# VF_Sine_CPU_Mainboard2.net
KiCad netlist of a schematic drawn in EAGLE
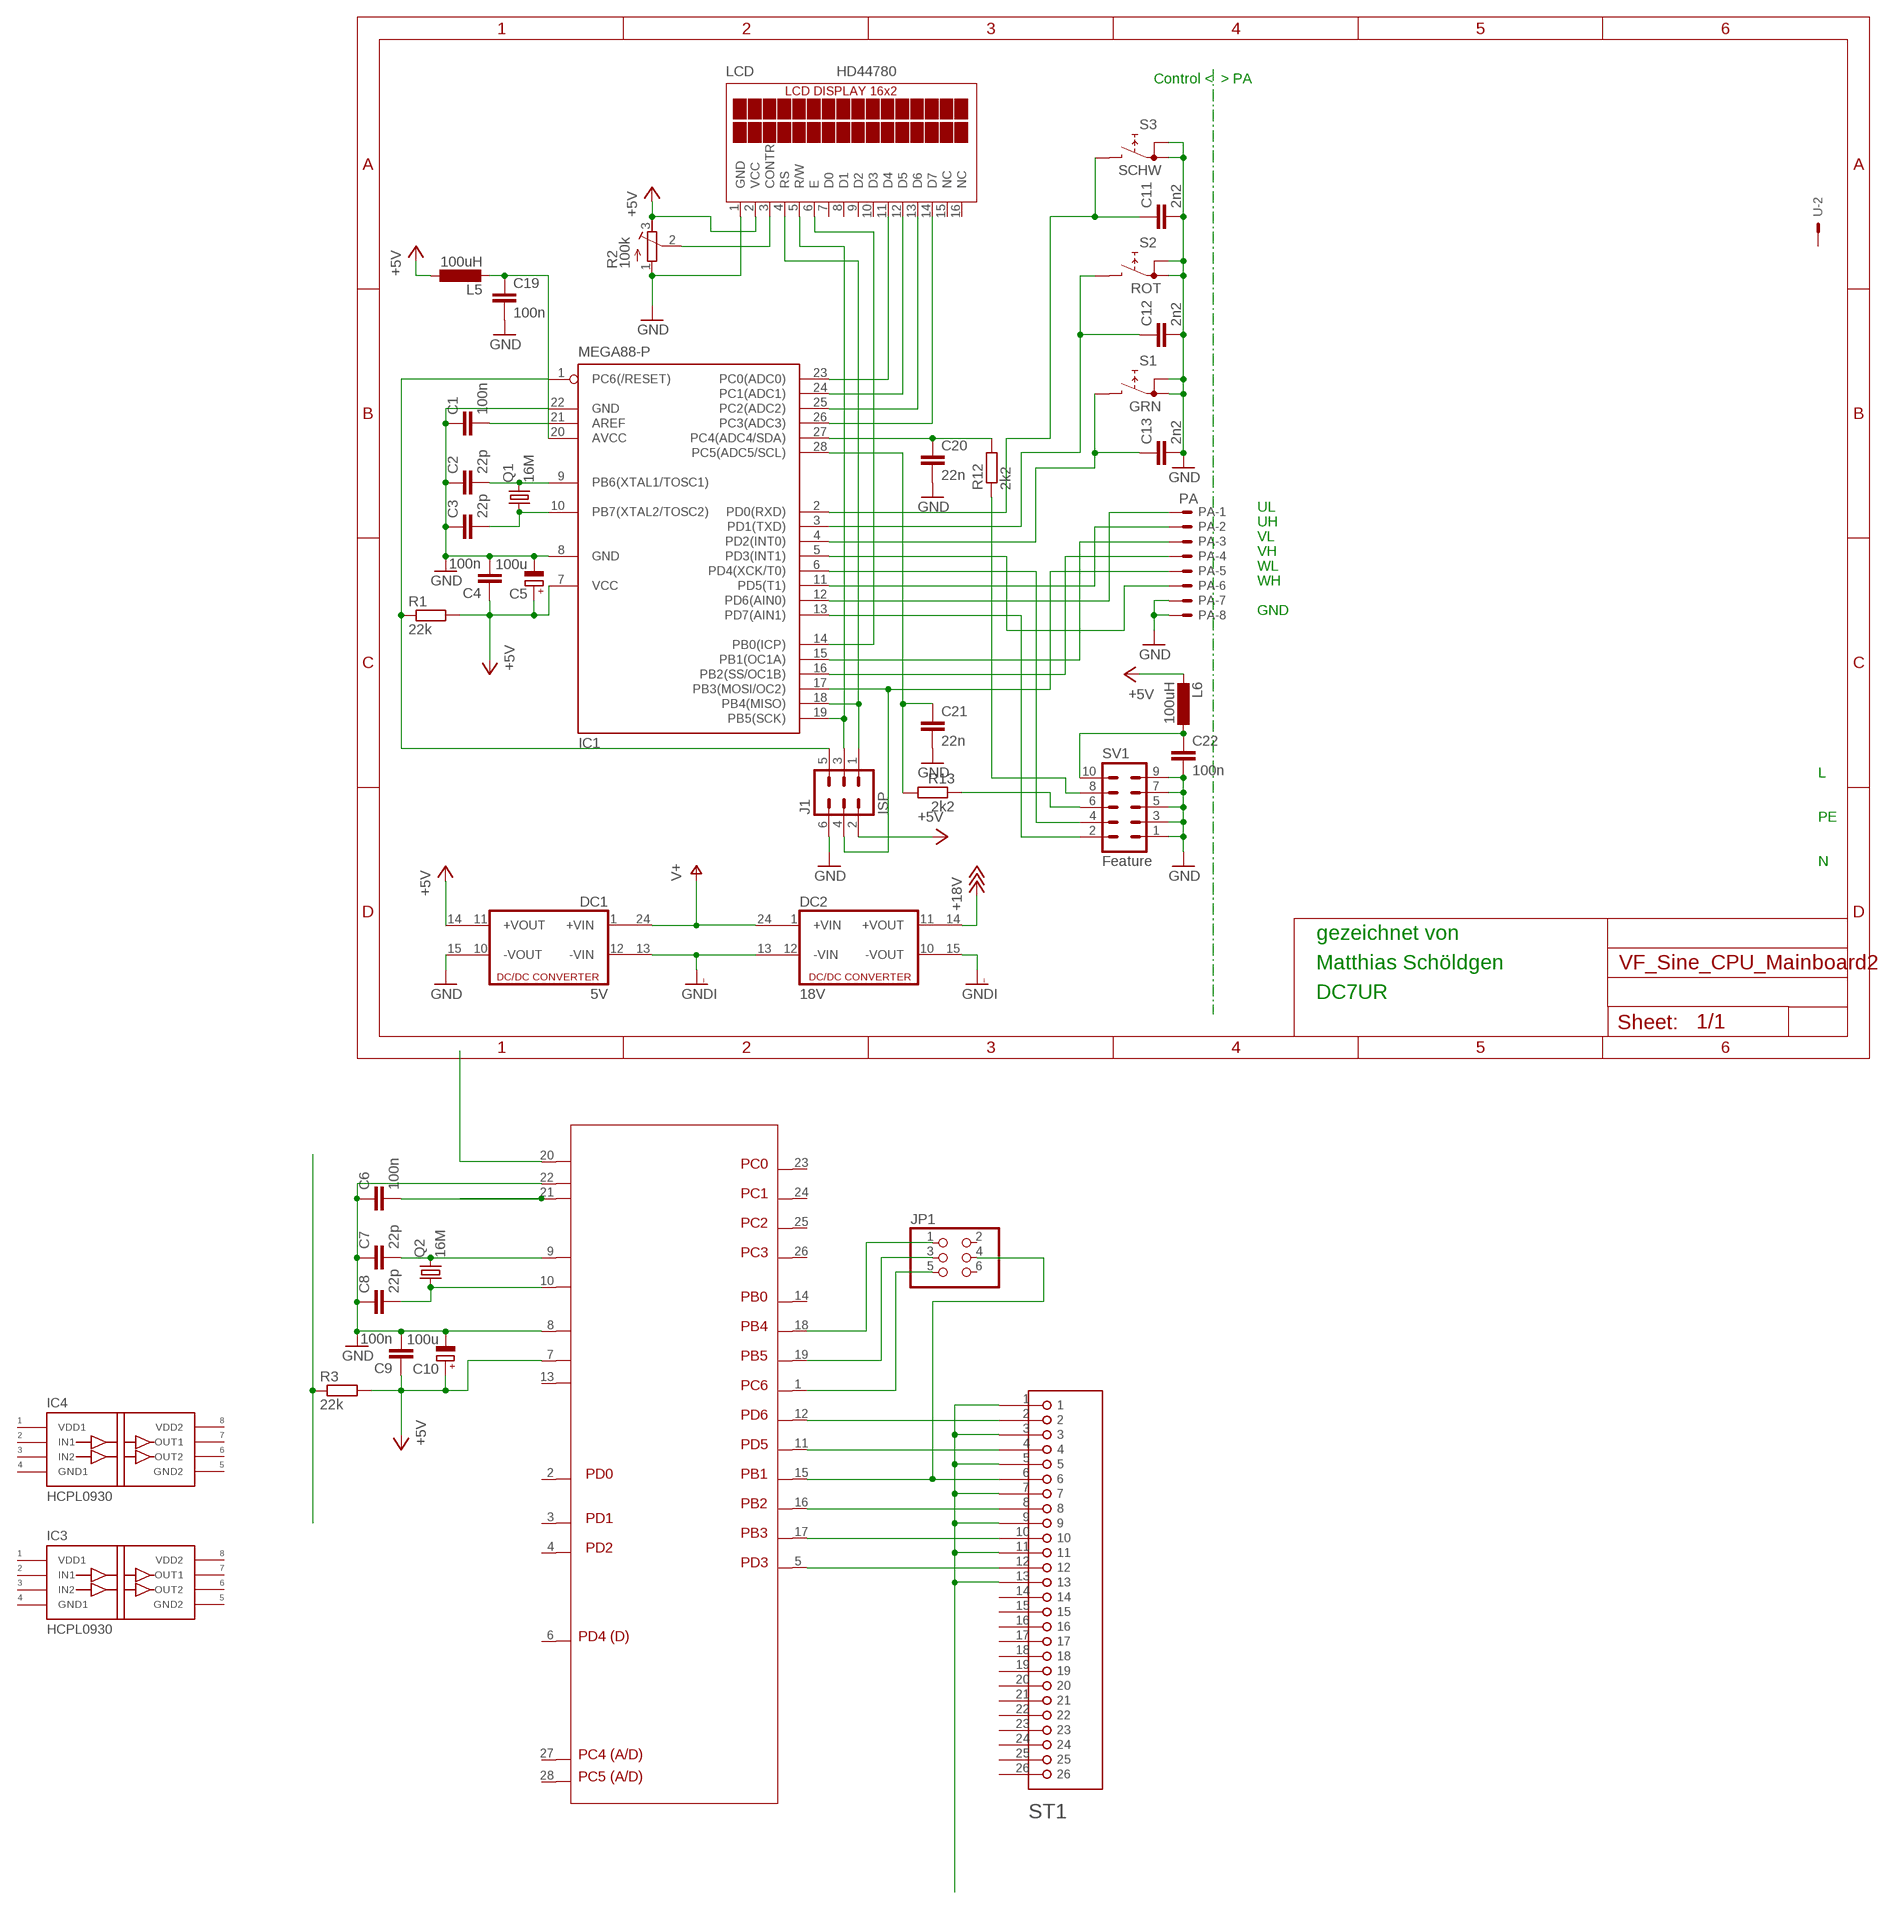
[diagram p0: schematic, sheet 1]

(export (version "E")
  (design (tool "Eeschema 10.0.6"))
  (components
    (comp (ref "C1")
      (value "100n")
      (footprint "eagle-import:C025-025X050")
      (libsource (lib "eagle-import") (part "C-EU025-025X050"))
    )
    (comp (ref "C2")
      (value "22p")
      (footprint "eagle-import:C025-025X050")
      (libsource (lib "eagle-import") (part "C-EU025-025X050"))
    )
    (comp (ref "C3")
      (value "22p")
      (footprint "eagle-import:C025-025X050")
      (libsource (lib "eagle-import") (part "C-EU025-025X050"))
    )
    (comp (ref "C4")
      (value "100n")
      (footprint "eagle-import:C025-025X050")
      (libsource (lib "eagle-import") (part "C-EU025-025X050"))
    )
    (comp (ref "C5")
      (value "100u")
      (footprint "eagle-import:B45181A")
      (libsource (lib "eagle-import") (part "CPOL-EUB45181A"))
    )
    (comp (ref "C6")
      (value "100n")
      (footprint "eagle-import:C025-025X050")
      (libsource (lib "eagle-import") (part "C-EU025-025X050"))
    )
    (comp (ref "C7")
      (value "22p")
      (footprint "eagle-import:C025-025X050")
      (libsource (lib "eagle-import") (part "C-EU025-025X050"))
    )
    (comp (ref "C8")
      (value "22p")
      (footprint "eagle-import:C025-025X050")
      (libsource (lib "eagle-import") (part "C-EU025-025X050"))
    )
    (comp (ref "C9")
      (value "100n")
      (footprint "eagle-import:C025-025X050")
      (libsource (lib "eagle-import") (part "C-EU025-025X050"))
    )
    (comp (ref "C10")
      (value "100u")
      (footprint "eagle-import:B45181A")
      (libsource (lib "eagle-import") (part "CPOL-EUB45181A"))
    )
    (comp (ref "C11")
      (value "2n2")
      (footprint "eagle-import:C025-025X050")
      (libsource (lib "eagle-import") (part "C-EU025-025X050"))
    )
    (comp (ref "C12")
      (value "2n2")
      (footprint "eagle-import:C025-025X050")
      (libsource (lib "eagle-import") (part "C-EU025-025X050"))
    )
    (comp (ref "C13")
      (value "2n2")
      (footprint "eagle-import:C025-025X050")
      (libsource (lib "eagle-import") (part "C-EU025-025X050"))
    )
    (comp (ref "C19")
      (value "100n")
      (footprint "eagle-import:C050-030X075")
      (libsource (lib "eagle-import") (part "C-EU050-030X075"))
    )
    (comp (ref "C20")
      (value "22n")
      (footprint "eagle-import:C025-024X044")
      (libsource (lib "eagle-import") (part "C-EU025-024X044"))
    )
    (comp (ref "C21")
      (value "22n")
      (footprint "eagle-import:C025-024X044")
      (libsource (lib "eagle-import") (part "C-EU025-024X044"))
    )
    (comp (ref "C22")
      (value "100n")
      (footprint "eagle-import:C025-025X050")
      (libsource (lib "eagle-import") (part "C-EU025-025X050"))
    )
    (comp (ref "DC1")
      (value "5V")
      (footprint "eagle-import:CMK")
      (libsource (lib "eagle-import") (part "DC213R"))
    )
    (comp (ref "DC2")
      (value "18V")
      (footprint "eagle-import:CMK")
      (libsource (lib "eagle-import") (part "DC213R"))
    )
    (comp (ref "IC1")
      (value "MEGA88-P")
      (footprint "eagle-import:DIL28-3")
      (libsource (lib "eagle-import") (part "MEGA8-P"))
    )
    (comp (ref "IC2")
      (value "ATMEGA328P_VAR")
      (footprint "eagle-import:DIL-28S")
      (libsource (lib "eagle-import") (part "ATMEGA328P_VAR"))
    )
    (comp (ref "IC3")
      (value "HCPL0930")
      (footprint "eagle-import:SO8")
      (libsource (lib "eagle-import") (part "HCPL0930"))
    )
    (comp (ref "IC4")
      (value "HCPL0930")
      (footprint "eagle-import:SO8")
      (libsource (lib "eagle-import") (part "HCPL0930"))
    )
    (comp (ref "J1")
      (value "ISP")
      (footprint "eagle-import:ML6")
      (libsource (lib "eagle-import") (part "ML6"))
    )
    (comp (ref "JP1")
      (value "PINHD-2X3")
      (footprint "eagle-import:2X03")
      (libsource (lib "eagle-import") (part "PINHD-2X3"))
    )
    (comp (ref "L5")
      (value "100uH")
      (footprint "eagle-import:0204_5")
      (libsource (lib "eagle-import") (part "L-EU0204/5"))
    )
    (comp (ref "L6")
      (value "100uH")
      (footprint "eagle-import:0204_5")
      (libsource (lib "eagle-import") (part "L-EU0204/5"))
    )
    (comp (ref "LCD")
      (value "HD44780")
      (footprint "eagle-import:TUXGR_16X2_R2")
      (libsource (lib "eagle-import") (part "TUXGR_16X2_R2"))
    )
    (comp (ref "PA")
      (value "PA")
      (footprint "eagle-import:22-23-2081")
      (libsource (lib "eagle-import") (part "22-23-2081"))
    )
    (comp (ref "Q1")
      (value "16M")
      (footprint "eagle-import:HC49_S")
      (libsource (lib "eagle-import") (part "CRYSTALHC49S"))
    )
    (comp (ref "Q2")
      (value "16M")
      (footprint "eagle-import:HC49_S")
      (libsource (lib "eagle-import") (part "CRYSTALHC49S"))
    )
    (comp (ref "R1")
      (value "22k")
      (footprint "eagle-import:0207_2V")
      (libsource (lib "eagle-import") (part "R-EU_0207/2V"))
    )
    (comp (ref "R2")
      (value "100k")
      (footprint "eagle-import:RTRIM4G_J")
      (libsource (lib "eagle-import") (part "R-TRIMM4G/J"))
    )
    (comp (ref "R3")
      (value "22k")
      (footprint "eagle-import:0207_2V")
      (libsource (lib "eagle-import") (part "R-EU_0207/2V"))
    )
    (comp (ref "R12")
      (value "2k2")
      (footprint "eagle-import:0204_5")
      (libsource (lib "eagle-import") (part "R-EU_0204/5"))
    )
    (comp (ref "R13")
      (value "2k2")
      (footprint "eagle-import:0204_5")
      (libsource (lib "eagle-import") (part "R-EU_0204/5"))
    )
    (comp (ref "S1")
      (value "GRN")
      (footprint "eagle-import:RDT1034")
      (libsource (lib "eagle-import") (part "RDT1034"))
    )
    (comp (ref "S2")
      (value "ROT")
      (footprint "eagle-import:RDT1034")
      (libsource (lib "eagle-import") (part "RDT1034"))
    )
    (comp (ref "S3")
      (value "SCHW")
      (footprint "eagle-import:RDT1034")
      (libsource (lib "eagle-import") (part "RDT1034"))
    )
    (comp (ref "ST1")
      (value "HD-26")
      (footprint "eagle-import:HD-26")
      (libsource (lib "eagle-import") (part "HD-26"))
    )
    (comp (ref "SV1")
      (value "Feature")
      (footprint "eagle-import:ML10")
      (libsource (lib "eagle-import") (part "ML10"))
    )
    (comp (ref "U")
      (value "5566-2")
      (footprint "eagle-import:5566-2")
      (libsource (lib "eagle-import") (part "5566-2"))
    )
  )
  (nets
    (net (code "1") (name "+5V") (class "Default")
      (node (ref "C10") (pin "+") (pinfunction "+_+") (pintype "passive"))
      (node (ref "C4") (pin "1") (pinfunction "1_1") (pintype "passive"))
      (node (ref "C5") (pin "+") (pinfunction "+_+") (pintype "passive"))
      (node (ref "C9") (pin "1") (pinfunction "1_1") (pintype "passive"))
      (node (ref "DC1") (pin "14") (pinfunction "+VOUT1_14") (pintype "passive"))
      (node (ref "IC1") (pin "7") (pinfunction "VCC_7") (pintype "power_in"))
      (node (ref "IC2") (pin "7") (pinfunction "SK1_7") (pintype "passive"))
      (node (ref "J1") (pin "2") (pinfunction "2_2") (pintype "passive"))
      (node (ref "L5") (pin "1") (pinfunction "1_1") (pintype "passive"))
      (node (ref "L6") (pin "2") (pinfunction "2_2") (pintype "passive"))
      (node (ref "LCD") (pin "2") (pinfunction "VCC_2") (pintype "power_in"))
      (node (ref "R1") (pin "2") (pinfunction "2_2") (pintype "passive"))
      (node (ref "R2") (pin "3") (pinfunction "A_3") (pintype "passive"))
      (node (ref "R3") (pin "2") (pinfunction "2_2") (pintype "passive"))
    )
    (net (code "2") (name "+18V") (class "Default")
      (node (ref "DC2") (pin "14") (pinfunction "+VOUT1_14") (pintype "passive"))
    )
    (net (code "3") (name "GND") (class "Default")
      (node (ref "C1") (pin "1") (pinfunction "1_1") (pintype "passive"))
      (node (ref "C10") (pin "-") (pinfunction "-_-") (pintype "passive"))
      (node (ref "C11") (pin "2") (pinfunction "2_2") (pintype "passive"))
      (node (ref "C12") (pin "2") (pinfunction "2_2") (pintype "passive"))
      (node (ref "C13") (pin "2") (pinfunction "2_2") (pintype "passive"))
      (node (ref "C19") (pin "2") (pinfunction "2_2") (pintype "passive"))
      (node (ref "C2") (pin "1") (pinfunction "1_1") (pintype "passive"))
      (node (ref "C20") (pin "2") (pinfunction "2_2") (pintype "passive"))
      (node (ref "C21") (pin "2") (pinfunction "2_2") (pintype "passive"))
      (node (ref "C22") (pin "2") (pinfunction "2_2") (pintype "passive"))
      (node (ref "C3") (pin "1") (pinfunction "1_1") (pintype "passive"))
      (node (ref "C4") (pin "2") (pinfunction "2_2") (pintype "passive"))
      (node (ref "C5") (pin "-") (pinfunction "-_-") (pintype "passive"))
      (node (ref "C6") (pin "1") (pinfunction "1_1") (pintype "passive"))
      (node (ref "C7") (pin "1") (pinfunction "1_1") (pintype "passive"))
      (node (ref "C8") (pin "1") (pinfunction "1_1") (pintype "passive"))
      (node (ref "C9") (pin "2") (pinfunction "2_2") (pintype "passive"))
      (node (ref "DC1") (pin "15") (pinfunction "-VOUT1_15") (pintype "passive"))
      (node (ref "IC1") (pin "22") (pinfunction "GND_22") (pintype "power_in"))
      (node (ref "IC1") (pin "8") (pinfunction "GND_8") (pintype "power_in"))
      (node (ref "IC2") (pin "22") (pinfunction "SK1_22") (pintype "passive"))
      (node (ref "IC2") (pin "8") (pinfunction "SK1_8") (pintype "passive"))
      (node (ref "J1") (pin "6") (pinfunction "6_6") (pintype "passive"))
      (node (ref "LCD") (pin "1") (pinfunction "GND_1") (pintype "power_in"))
      (node (ref "PA") (pin "7") (pinfunction "S_7") (pintype "passive"))
      (node (ref "PA") (pin "8") (pinfunction "S_8") (pintype "passive"))
      (node (ref "R2") (pin "1") (pinfunction "E_1") (pintype "passive"))
      (node (ref "S1") (pin "A") (pinfunction "A_A") (pintype "passive"))
      (node (ref "S1") (pin "A1") (pinfunction "A1_A1") (pintype "passive"))
      (node (ref "S2") (pin "A") (pinfunction "A_A") (pintype "passive"))
      (node (ref "S2") (pin "A1") (pinfunction "A1_A1") (pintype "passive"))
      (node (ref "S3") (pin "A") (pinfunction "A_A") (pintype "passive"))
      (node (ref "S3") (pin "A1") (pinfunction "A1_A1") (pintype "passive"))
      (node (ref "SV1") (pin "1") (pinfunction "1_1") (pintype "passive"))
      (node (ref "SV1") (pin "3") (pinfunction "3_3") (pintype "passive"))
      (node (ref "SV1") (pin "5") (pinfunction "5_5") (pintype "passive"))
      (node (ref "SV1") (pin "7") (pinfunction "7_7") (pintype "passive"))
      (node (ref "SV1") (pin "9") (pinfunction "9_9") (pintype "passive"))
    )
    (net (code "4") (name "GNDI") (class "Default")
      (node (ref "DC1") (pin "13") (pinfunction "-VIN1_13") (pintype "passive"))
      (node (ref "DC2") (pin "13") (pinfunction "-VIN1_13") (pintype "passive"))
      (node (ref "DC2") (pin "15") (pinfunction "-VOUT1_15") (pintype "passive"))
    )
    (net (code "5") (name "Net-(C22-Pad1)") (class "Default")
      (node (ref "C22") (pin "1") (pinfunction "1_1") (pintype "passive"))
      (node (ref "L6") (pin "1") (pinfunction "1_1") (pintype "passive"))
      (node (ref "SV1") (pin "10") (pinfunction "10_10") (pintype "passive"))
    )
    (net (code "6") (name "Net-(IC1-AREF)") (class "Default")
      (node (ref "C1") (pin "2") (pinfunction "2_2") (pintype "passive"))
      (node (ref "IC1") (pin "21") (pinfunction "AREF_21") (pintype "passive"))
    )
    (net (code "7") (name "Net-(IC1-AVCC)") (class "Default")
      (node (ref "C19") (pin "1") (pinfunction "1_1") (pintype "passive"))
      (node (ref "IC1") (pin "20") (pinfunction "AVCC_20") (pintype "power_in"))
      (node (ref "L5") (pin "2") (pinfunction "2_2") (pintype "passive"))
    )
    (net (code "8") (name "Net-(IC1-PB0(ICP))") (class "Default")
      (node (ref "IC1") (pin "14") (pinfunction "PB0(ICP)_14") (pintype "bidirectional"))
      (node (ref "LCD") (pin "6") (pinfunction "E_6") (pintype "input"))
    )
    (net (code "9") (name "Net-(IC1-PB1(OC1A))") (class "Default")
      (node (ref "IC1") (pin "15") (pinfunction "PB1(OC1A)_15") (pintype "bidirectional"))
      (node (ref "PA") (pin "3") (pinfunction "S_3") (pintype "passive"))
    )
    (net (code "10") (name "Net-(IC1-PB2(SS{slash}OC1B))") (class "Default")
      (node (ref "IC1") (pin "16") (pinfunction "PB2(SS/OC1B)_16") (pintype "bidirectional"))
      (node (ref "PA") (pin "4") (pinfunction "S_4") (pintype "passive"))
    )
    (net (code "11") (name "Net-(IC1-PB3(MOSI{slash}OC2))") (class "Default")
      (node (ref "IC1") (pin "17") (pinfunction "PB3(MOSI/OC2)_17") (pintype "bidirectional"))
      (node (ref "J1") (pin "4") (pinfunction "4_4") (pintype "passive"))
      (node (ref "PA") (pin "5") (pinfunction "S_5") (pintype "passive"))
    )
    (net (code "12") (name "Net-(IC1-PB4(MISO))") (class "Default")
      (node (ref "IC1") (pin "18") (pinfunction "PB4(MISO)_18") (pintype "bidirectional"))
      (node (ref "J1") (pin "1") (pinfunction "1_1") (pintype "passive"))
      (node (ref "LCD") (pin "4") (pinfunction "RS_4") (pintype "input"))
    )
    (net (code "13") (name "Net-(IC1-PB5(SCK))") (class "Default")
      (node (ref "IC1") (pin "19") (pinfunction "PB5(SCK)_19") (pintype "bidirectional"))
      (node (ref "J1") (pin "3") (pinfunction "3_3") (pintype "passive"))
      (node (ref "LCD") (pin "5") (pinfunction "R/W_5") (pintype "input"))
    )
    (net (code "14") (name "Net-(IC1-PB6(XTAL1{slash}TOSC1))") (class "Default")
      (node (ref "C2") (pin "2") (pinfunction "2_2") (pintype "passive"))
      (node (ref "IC1") (pin "9") (pinfunction "PB6(XTAL1/TOSC1)_9") (pintype "bidirectional"))
      (node (ref "Q1") (pin "2") (pinfunction "2_2") (pintype "passive"))
    )
    (net (code "15") (name "Net-(IC1-PB7(XTAL2{slash}TOSC2))") (class "Default")
      (node (ref "C3") (pin "2") (pinfunction "2_2") (pintype "passive"))
      (node (ref "IC1") (pin "10") (pinfunction "PB7(XTAL2/TOSC2)_10") (pintype "bidirectional"))
      (node (ref "Q1") (pin "1") (pinfunction "1_1") (pintype "passive"))
    )
    (net (code "16") (name "Net-(IC1-PC0(ADC0))") (class "Default")
      (node (ref "IC1") (pin "23") (pinfunction "PC0(ADC0)_23") (pintype "bidirectional"))
      (node (ref "LCD") (pin "11") (pinfunction "D4_11") (pintype "input"))
    )
    (net (code "17") (name "Net-(IC1-PC1(ADC1))") (class "Default")
      (node (ref "IC1") (pin "24") (pinfunction "PC1(ADC1)_24") (pintype "bidirectional"))
      (node (ref "LCD") (pin "12") (pinfunction "D5_12") (pintype "input"))
    )
    (net (code "18") (name "Net-(IC1-PC2(ADC2))") (class "Default")
      (node (ref "IC1") (pin "25") (pinfunction "PC2(ADC2)_25") (pintype "bidirectional"))
      (node (ref "LCD") (pin "13") (pinfunction "D6_13") (pintype "input"))
    )
    (net (code "19") (name "Net-(IC1-PC3(ADC3))") (class "Default")
      (node (ref "IC1") (pin "26") (pinfunction "PC3(ADC3)_26") (pintype "bidirectional"))
      (node (ref "LCD") (pin "14") (pinfunction "D7_14") (pintype "input"))
    )
    (net (code "20") (name "Net-(IC1-PC4(ADC4{slash}SDA))") (class "Default")
      (node (ref "C20") (pin "1") (pinfunction "1_1") (pintype "passive"))
      (node (ref "IC1") (pin "27") (pinfunction "PC4(ADC4/SDA)_27") (pintype "bidirectional"))
      (node (ref "R12") (pin "2") (pinfunction "2_2") (pintype "passive"))
    )
    (net (code "21") (name "Net-(IC1-PC5(ADC5{slash}SCL))") (class "Default")
      (node (ref "C21") (pin "1") (pinfunction "1_1") (pintype "passive"))
      (node (ref "IC1") (pin "28") (pinfunction "PC5(ADC5/SCL)_28") (pintype "bidirectional"))
      (node (ref "R13") (pin "2") (pinfunction "2_2") (pintype "passive"))
    )
    (net (code "22") (name "Net-(IC1-PC6({slash}RESET))") (class "Default")
      (node (ref "IC1") (pin "1") (pinfunction "PC6(/RESET)_1") (pintype "bidirectional"))
      (node (ref "J1") (pin "5") (pinfunction "5_5") (pintype "passive"))
      (node (ref "R1") (pin "1") (pinfunction "1_1") (pintype "passive"))
    )
    (net (code "23") (name "Net-(IC1-PD0(RXD))") (class "Default")
      (node (ref "C11") (pin "1") (pinfunction "1_1") (pintype "passive"))
      (node (ref "IC1") (pin "2") (pinfunction "PD0(RXD)_2") (pintype "bidirectional"))
      (node (ref "S3") (pin "B") (pinfunction "B_B") (pintype "passive"))
    )
    (net (code "24") (name "Net-(IC1-PD1(TXD))") (class "Default")
      (node (ref "C12") (pin "1") (pinfunction "1_1") (pintype "passive"))
      (node (ref "IC1") (pin "3") (pinfunction "PD1(TXD)_3") (pintype "bidirectional"))
      (node (ref "S2") (pin "B") (pinfunction "B_B") (pintype "passive"))
    )
    (net (code "25") (name "Net-(IC1-PD2(INT0))") (class "Default")
      (node (ref "C13") (pin "1") (pinfunction "1_1") (pintype "passive"))
      (node (ref "IC1") (pin "4") (pinfunction "PD2(INT0)_4") (pintype "bidirectional"))
      (node (ref "S1") (pin "B") (pinfunction "B_B") (pintype "passive"))
    )
    (net (code "26") (name "Net-(IC1-PD3(INT1))") (class "Default")
      (node (ref "IC1") (pin "5") (pinfunction "PD3(INT1)_5") (pintype "bidirectional"))
      (node (ref "PA") (pin "6") (pinfunction "S_6") (pintype "passive"))
    )
    (net (code "27") (name "Net-(IC1-PD4(XCK{slash}T0))") (class "Default")
      (node (ref "IC1") (pin "6") (pinfunction "PD4(XCK/T0)_6") (pintype "bidirectional"))
      (node (ref "SV1") (pin "4") (pinfunction "4_4") (pintype "passive"))
    )
    (net (code "28") (name "Net-(IC1-PD5(T1))") (class "Default")
      (node (ref "IC1") (pin "11") (pinfunction "PD5(T1)_11") (pintype "bidirectional"))
      (node (ref "PA") (pin "2") (pinfunction "S_2") (pintype "passive"))
    )
    (net (code "29") (name "Net-(IC1-PD6(AIN0))") (class "Default")
      (node (ref "IC1") (pin "12") (pinfunction "PD6(AIN0)_12") (pintype "bidirectional"))
      (node (ref "PA") (pin "1") (pinfunction "S_1") (pintype "passive"))
    )
    (net (code "30") (name "Net-(IC1-PD7(AIN1))") (class "Default")
      (node (ref "IC1") (pin "13") (pinfunction "PD7(AIN1)_13") (pintype "bidirectional"))
      (node (ref "SV1") (pin "2") (pinfunction "2_2") (pintype "passive"))
    )
    (net (code "31") (name "Net-(IC2A-SK1)") (class "Default")
      (node (ref "IC2") (pin "1") (pinfunction "SK1_1") (pintype "passive"))
      (node (ref "JP1") (pin "5") (pinfunction "5_5") (pintype "passive"))
    )
    (net (code "32") (name "Net-(IC2AB-SK1)") (class "Default")
      (node (ref "C7") (pin "2") (pinfunction "2_2") (pintype "passive"))
      (node (ref "IC2") (pin "9") (pinfunction "SK1_9") (pintype "passive"))
      (node (ref "Q2") (pin "2") (pinfunction "2_2") (pintype "passive"))
    )
    (net (code "33") (name "Net-(IC2B-SK1)") (class "Default")
      (node (ref "C8") (pin "2") (pinfunction "2_2") (pintype "passive"))
      (node (ref "IC2") (pin "10") (pinfunction "SK1_10") (pintype "passive"))
      (node (ref "Q2") (pin "1") (pinfunction "1_1") (pintype "passive"))
    )
    (net (code "34") (name "Net-(IC2C-SK1)") (class "Default")
      (node (ref "IC2") (pin "11") (pinfunction "SK1_11") (pintype "passive"))
      (node (ref "ST1") (pin "4") (pinfunction "4_4") (pintype "bidirectional"))
    )
    (net (code "35") (name "Net-(IC2D-SK1)") (class "Default")
      (node (ref "IC2") (pin "12") (pinfunction "SK1_12") (pintype "passive"))
      (node (ref "ST1") (pin "2") (pinfunction "2_2") (pintype "bidirectional"))
    )
    (net (code "36") (name "Net-(IC2G-SK1)") (class "Default")
      (node (ref "IC2") (pin "15") (pinfunction "SK1_15") (pintype "passive"))
      (node (ref "JP1") (pin "4") (pinfunction "4_4") (pintype "passive"))
      (node (ref "ST1") (pin "6") (pinfunction "6_6") (pintype "bidirectional"))
    )
    (net (code "37") (name "Net-(IC2H-SK1)") (class "Default")
      (node (ref "IC2") (pin "16") (pinfunction "SK1_16") (pintype "passive"))
      (node (ref "ST1") (pin "8") (pinfunction "8_8") (pintype "bidirectional"))
    )
    (net (code "38") (name "Net-(IC2I-SK1)") (class "Default")
      (node (ref "IC2") (pin "17") (pinfunction "SK1_17") (pintype "passive"))
      (node (ref "ST1") (pin "10") (pinfunction "10_10") (pintype "bidirectional"))
    )
    (net (code "39") (name "Net-(IC2J-SK1)") (class "Default")
      (node (ref "IC2") (pin "18") (pinfunction "SK1_18") (pintype "passive"))
      (node (ref "JP1") (pin "1") (pinfunction "1_1") (pintype "passive"))
    )
    (net (code "40") (name "Net-(IC2K-SK1)") (class "Default")
      (node (ref "IC2") (pin "19") (pinfunction "SK1_19") (pintype "passive"))
      (node (ref "JP1") (pin "3") (pinfunction "3_3") (pintype "passive"))
    )
    (net (code "41") (name "Net-(IC2N-SK1)") (class "Default")
      (node (ref "C6") (pin "2") (pinfunction "2_2") (pintype "passive"))
      (node (ref "IC2") (pin "21") (pinfunction "SK1_21") (pintype "passive"))
    )
    (net (code "42") (name "Net-(IC2X-SK1)") (class "Default")
      (node (ref "IC2") (pin "5") (pinfunction "SK1_5") (pintype "passive"))
      (node (ref "ST1") (pin "12") (pinfunction "12_12") (pintype "bidirectional"))
    )
    (net (code "43") (name "Net-(LCD-CONTR)") (class "Default")
      (node (ref "LCD") (pin "3") (pinfunction "CONTR_3") (pintype "input"))
      (node (ref "R2") (pin "2") (pinfunction "S_2") (pintype "passive"))
    )
    (net (code "44") (name "Net-(R12-Pad1)") (class "Default")
      (node (ref "R12") (pin "1") (pinfunction "1_1") (pintype "passive"))
      (node (ref "SV1") (pin "8") (pinfunction "8_8") (pintype "passive"))
    )
    (net (code "45") (name "Net-(R13-Pad1)") (class "Default")
      (node (ref "R13") (pin "1") (pinfunction "1_1") (pintype "passive"))
      (node (ref "SV1") (pin "6") (pinfunction "6_6") (pintype "passive"))
    )
    (net (code "46") (name "Net-(ST1-Pad1)") (class "Default")
      (node (ref "ST1") (pin "1") (pinfunction "1_1") (pintype "bidirectional"))
      (node (ref "ST1") (pin "11") (pinfunction "11_11") (pintype "bidirectional"))
      (node (ref "ST1") (pin "13") (pinfunction "13_13") (pintype "bidirectional"))
      (node (ref "ST1") (pin "3") (pinfunction "3_3") (pintype "bidirectional"))
      (node (ref "ST1") (pin "5") (pinfunction "5_5") (pintype "bidirectional"))
      (node (ref "ST1") (pin "7") (pinfunction "7_7") (pintype "bidirectional"))
      (node (ref "ST1") (pin "9") (pinfunction "9_9") (pintype "bidirectional"))
    )
    (net (code "47") (name "V+") (class "Default")
      (node (ref "DC1") (pin "24") (pinfunction "+VIN1_24") (pintype "passive"))
      (node (ref "DC2") (pin "24") (pinfunction "+VIN1_24") (pintype "passive"))
    )
    (net (code "48") (name "unconnected-(DC1-+VIN-Pad1)") (class "Default")
      (node (ref "DC1") (pin "1") (pinfunction "+VIN_1") (pintype "passive"))
    )
    (net (code "49") (name "unconnected-(DC1-+VOUT-Pad11)") (class "Default")
      (node (ref "DC1") (pin "11") (pinfunction "+VOUT_11") (pintype "passive"))
    )
    (net (code "50") (name "unconnected-(DC1--VIN-Pad12)") (class "Default")
      (node (ref "DC1") (pin "12") (pinfunction "-VIN_12") (pintype "passive"))
    )
    (net (code "51") (name "unconnected-(DC1--VOUT-Pad10)") (class "Default")
      (node (ref "DC1") (pin "10") (pinfunction "-VOUT_10") (pintype "passive"))
    )
    (net (code "52") (name "unconnected-(DC2-+VIN-Pad1)") (class "Default")
      (node (ref "DC2") (pin "1") (pinfunction "+VIN_1") (pintype "passive"))
    )
    (net (code "53") (name "unconnected-(DC2-+VOUT-Pad11)") (class "Default")
      (node (ref "DC2") (pin "11") (pinfunction "+VOUT_11") (pintype "passive"))
    )
    (net (code "54") (name "unconnected-(DC2--VIN-Pad12)") (class "Default")
      (node (ref "DC2") (pin "12") (pinfunction "-VIN_12") (pintype "passive"))
    )
    (net (code "55") (name "unconnected-(DC2--VOUT-Pad10)") (class "Default")
      (node (ref "DC2") (pin "10") (pinfunction "-VOUT_10") (pintype "passive"))
    )
    (net (code "56") (name "unconnected-(IC2E-SK1-Pad13)") (class "Default")
      (node (ref "IC2") (pin "13") (pinfunction "SK1_13") (pintype "passive"))
    )
    (net (code "57") (name "unconnected-(IC2F-SK1-Pad14)") (class "Default")
      (node (ref "IC2") (pin "14") (pinfunction "SK1_14") (pintype "passive"))
    )
    (net (code "58") (name "unconnected-(IC2L-SK1-Pad2)") (class "Default")
      (node (ref "IC2") (pin "2") (pinfunction "SK1_2") (pintype "passive"))
    )
    (net (code "59") (name "unconnected-(IC2M-SK1-Pad20)") (class "Default")
      (node (ref "IC2") (pin "20") (pinfunction "SK1_20") (pintype "passive"))
    )
    (net (code "60") (name "unconnected-(IC2P-SK1-Pad23)") (class "Default")
      (node (ref "IC2") (pin "23") (pinfunction "SK1_23") (pintype "passive"))
    )
    (net (code "61") (name "unconnected-(IC2Q-SK1-Pad24)") (class "Default")
      (node (ref "IC2") (pin "24") (pinfunction "SK1_24") (pintype "passive"))
    )
    (net (code "62") (name "unconnected-(IC2R-SK1-Pad25)") (class "Default")
      (node (ref "IC2") (pin "25") (pinfunction "SK1_25") (pintype "passive"))
    )
    (net (code "63") (name "unconnected-(IC2S-SK1-Pad26)") (class "Default")
      (node (ref "IC2") (pin "26") (pinfunction "SK1_26") (pintype "passive"))
    )
    (net (code "64") (name "unconnected-(IC2T-SK1-Pad27)") (class "Default")
      (node (ref "IC2") (pin "27") (pinfunction "SK1_27") (pintype "passive"))
    )
    (net (code "65") (name "unconnected-(IC2U-SK1-Pad28)") (class "Default")
      (node (ref "IC2") (pin "28") (pinfunction "SK1_28") (pintype "passive"))
    )
    (net (code "66") (name "unconnected-(IC2V-SK1-Pad3)") (class "Default")
      (node (ref "IC2") (pin "3") (pinfunction "SK1_3") (pintype "passive"))
    )
    (net (code "67") (name "unconnected-(IC2W-SK1-Pad4)") (class "Default")
      (node (ref "IC2") (pin "4") (pinfunction "SK1_4") (pintype "passive"))
    )
    (net (code "68") (name "unconnected-(IC2Y-SK1-Pad6)") (class "Default")
      (node (ref "IC2") (pin "6") (pinfunction "SK1_6") (pintype "passive"))
    )
    (net (code "69") (name "unconnected-(IC3-Pad1)") (class "Default")
      (node (ref "IC3") (pin "1") (pinfunction "1_1") (pintype "bidirectional"))
    )
    (net (code "70") (name "unconnected-(IC3-Pad2)") (class "Default")
      (node (ref "IC3") (pin "2") (pinfunction "2_2") (pintype "bidirectional"))
    )
    (net (code "71") (name "unconnected-(IC3-Pad3)") (class "Default")
      (node (ref "IC3") (pin "3") (pinfunction "3_3") (pintype "bidirectional"))
    )
    (net (code "72") (name "unconnected-(IC3-Pad4)") (class "Default")
      (node (ref "IC3") (pin "4") (pinfunction "4_4") (pintype "bidirectional"))
    )
    (net (code "73") (name "unconnected-(IC3-Pad5)") (class "Default")
      (node (ref "IC3") (pin "5") (pinfunction "5_5") (pintype "bidirectional"))
    )
    (net (code "74") (name "unconnected-(IC3-Pad6)") (class "Default")
      (node (ref "IC3") (pin "6") (pinfunction "6_6") (pintype "bidirectional"))
    )
    (net (code "75") (name "unconnected-(IC3-Pad7)") (class "Default")
      (node (ref "IC3") (pin "7") (pinfunction "7_7") (pintype "bidirectional"))
    )
    (net (code "76") (name "unconnected-(IC3-Pad8)") (class "Default")
      (node (ref "IC3") (pin "8") (pinfunction "8_8") (pintype "bidirectional"))
    )
    (net (code "77") (name "unconnected-(IC4-Pad1)") (class "Default")
      (node (ref "IC4") (pin "1") (pinfunction "1_1") (pintype "bidirectional"))
    )
    (net (code "78") (name "unconnected-(IC4-Pad2)") (class "Default")
      (node (ref "IC4") (pin "2") (pinfunction "2_2") (pintype "bidirectional"))
    )
    (net (code "79") (name "unconnected-(IC4-Pad3)") (class "Default")
      (node (ref "IC4") (pin "3") (pinfunction "3_3") (pintype "bidirectional"))
    )
    (net (code "80") (name "unconnected-(IC4-Pad4)") (class "Default")
      (node (ref "IC4") (pin "4") (pinfunction "4_4") (pintype "bidirectional"))
    )
    (net (code "81") (name "unconnected-(IC4-Pad5)") (class "Default")
      (node (ref "IC4") (pin "5") (pinfunction "5_5") (pintype "bidirectional"))
    )
    (net (code "82") (name "unconnected-(IC4-Pad6)") (class "Default")
      (node (ref "IC4") (pin "6") (pinfunction "6_6") (pintype "bidirectional"))
    )
    (net (code "83") (name "unconnected-(IC4-Pad7)") (class "Default")
      (node (ref "IC4") (pin "7") (pinfunction "7_7") (pintype "bidirectional"))
    )
    (net (code "84") (name "unconnected-(IC4-Pad8)") (class "Default")
      (node (ref "IC4") (pin "8") (pinfunction "8_8") (pintype "bidirectional"))
    )
    (net (code "85") (name "unconnected-(JP1-Pad2)") (class "Default")
      (node (ref "JP1") (pin "2") (pinfunction "2_2") (pintype "passive"))
    )
    (net (code "86") (name "unconnected-(JP1-Pad6)") (class "Default")
      (node (ref "JP1") (pin "6") (pinfunction "6_6") (pintype "passive"))
    )
    (net (code "87") (name "unconnected-(LCD-D0-Pad7)") (class "Default")
      (node (ref "LCD") (pin "7") (pinfunction "D0_7") (pintype "input"))
    )
    (net (code "88") (name "unconnected-(LCD-D1-Pad8)") (class "Default")
      (node (ref "LCD") (pin "8") (pinfunction "D1_8") (pintype "input"))
    )
    (net (code "89") (name "unconnected-(LCD-D2-Pad9)") (class "Default")
      (node (ref "LCD") (pin "9") (pinfunction "D2_9") (pintype "input"))
    )
    (net (code "90") (name "unconnected-(LCD-D3-Pad10)") (class "Default")
      (node (ref "LCD") (pin "10") (pinfunction "D3_10") (pintype "input"))
    )
    (net (code "91") (name "unconnected-(LCD-NC-Pad15)") (class "Default")
      (node (ref "LCD") (pin "15") (pinfunction "NC_15") (pintype "no_connect"))
    )
    (net (code "92") (name "unconnected-(LCD-NC-Pad16)") (class "Default")
      (node (ref "LCD") (pin "16") (pinfunction "NC_16") (pintype "no_connect"))
    )
    (net (code "93") (name "unconnected-(R3-Pad1)") (class "Default")
      (node (ref "R3") (pin "1") (pinfunction "1_1") (pintype "passive"))
    )
    (net (code "94") (name "unconnected-(ST1-Pad14)") (class "Default")
      (node (ref "ST1") (pin "14") (pinfunction "14_14") (pintype "bidirectional"))
    )
    (net (code "95") (name "unconnected-(ST1-Pad15)") (class "Default")
      (node (ref "ST1") (pin "15") (pinfunction "15_15") (pintype "bidirectional"))
    )
    (net (code "96") (name "unconnected-(ST1-Pad16)") (class "Default")
      (node (ref "ST1") (pin "16") (pinfunction "16_16") (pintype "bidirectional"))
    )
    (net (code "97") (name "unconnected-(ST1-Pad17)") (class "Default")
      (node (ref "ST1") (pin "17") (pinfunction "17_17") (pintype "bidirectional"))
    )
    (net (code "98") (name "unconnected-(ST1-Pad18)") (class "Default")
      (node (ref "ST1") (pin "18") (pinfunction "18_18") (pintype "bidirectional"))
    )
    (net (code "99") (name "unconnected-(ST1-Pad19)") (class "Default")
      (node (ref "ST1") (pin "19") (pinfunction "19_19") (pintype "bidirectional"))
    )
    (net (code "100") (name "unconnected-(ST1-Pad20)") (class "Default")
      (node (ref "ST1") (pin "20") (pinfunction "20_20") (pintype "bidirectional"))
    )
    (net (code "101") (name "unconnected-(ST1-Pad21)") (class "Default")
      (node (ref "ST1") (pin "21") (pinfunction "21_21") (pintype "bidirectional"))
    )
    (net (code "102") (name "unconnected-(ST1-Pad22)") (class "Default")
      (node (ref "ST1") (pin "22") (pinfunction "22_22") (pintype "bidirectional"))
    )
    (net (code "103") (name "unconnected-(ST1-Pad23)") (class "Default")
      (node (ref "ST1") (pin "23") (pinfunction "23_23") (pintype "bidirectional"))
    )
    (net (code "104") (name "unconnected-(ST1-Pad24)") (class "Default")
      (node (ref "ST1") (pin "24") (pinfunction "24_24") (pintype "bidirectional"))
    )
    (net (code "105") (name "unconnected-(ST1-Pad25)") (class "Default")
      (node (ref "ST1") (pin "25") (pinfunction "25_25") (pintype "bidirectional"))
    )
    (net (code "106") (name "unconnected-(ST1-Pad26)") (class "Default")
      (node (ref "ST1") (pin "26") (pinfunction "26_26") (pintype "bidirectional"))
    )
    (net (code "107") (name "unconnected-(UB-S-Pad2)") (class "Default")
      (node (ref "U") (pin "2") (pinfunction "S_2") (pintype "passive"))
    )
  )
)
